# design.net
KiCad netlist of a schematic drawn in Altium Designer
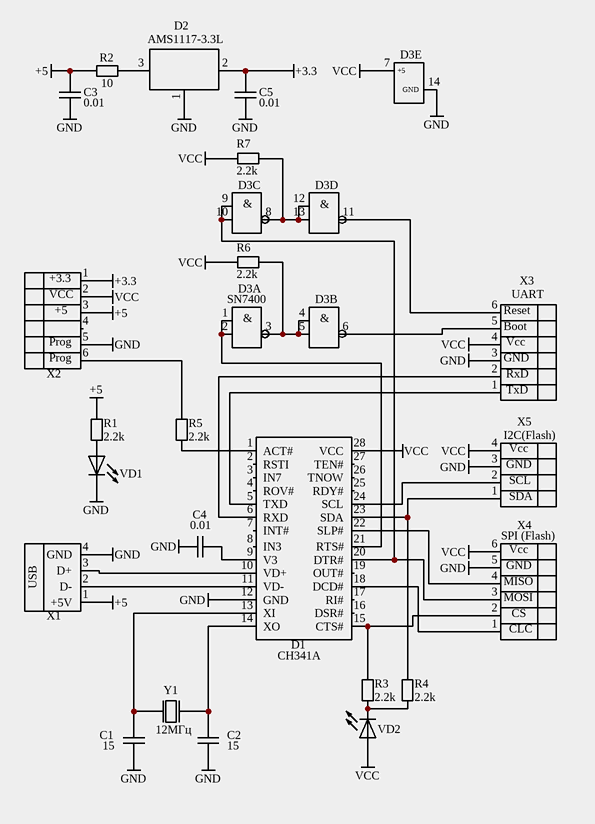
[diagram p0: схема.SchDoc]

(export (version "E")
  (design (tool "Eeschema 10.0.6"))
  (components
    (comp (ref "C1") (value "15") (footprint "0603") (libsource (lib "MainLib") (part "C")))
    (comp (ref "C2") (value "15") (footprint "0603") (libsource (lib "MainLib") (part "C")))
    (comp (ref "C3") (value "0.01") (footprint "0603") (libsource (lib "MainLib") (part "C")))
    (comp (ref "C4") (value "0.01") (footprint "0603") (libsource (lib "MainLib") (part "C")))
    (comp (ref "C5") (value "0.01") (footprint "0603") (libsource (lib "MainLib") (part "C")))
    (comp (ref "D1") (value "CH341A") (footprint "SOP127-28N") (libsource (lib "MainLib") (part "CH341A")))
    (comp (ref "D2")
      (value "AMS1117-3.3L")
      (footprint "SOT223-4N")
      (libsource (lib "MainLib") (part "AMS1117-3.3L"))
    )
    (comp (ref "D3") (value "SN7400") (footprint "SOP127-14N") (libsource (lib "MainLib") (part "SN7400")))
    (comp (ref "R1") (value "2.2k") (footprint "0603") (libsource (lib "MainLib") (part "R")))
    (comp (ref "R2") (value "10") (footprint "0603") (libsource (lib "MainLib") (part "R")))
    (comp (ref "R3") (value "2.2k") (footprint "0603") (libsource (lib "MainLib") (part "R")))
    (comp (ref "R4") (value "2.2k") (footprint "0603") (libsource (lib "MainLib") (part "R")))
    (comp (ref "R5") (value "2.2k") (footprint "0603") (libsource (lib "MainLib") (part "R")))
    (comp (ref "R6") (value "2.2k") (footprint "0603") (libsource (lib "MainLib") (part "R")))
    (comp (ref "R7") (value "2.2k") (footprint "0603") (libsource (lib "MainLib") (part "R")))
    (comp (ref "VD1")
      (value "LED SMD 0805")
      (footprint "Led Diode 0805")
      (libsource (lib "MainLib") (part "LED SMD 0805"))
    )
    (comp (ref "VD2")
      (value "LED SMD 0805")
      (footprint "Led Diode 0805")
      (libsource (lib "MainLib") (part "LED SMD 0805"))
    )
    (comp (ref "X1") (value "USB") (footprint "USB-ASM (DS1098-B)") (libsource (lib "MainLib") (part "USB")))
    (comp (ref "X2") (value "PLC-6") (footprint "PLC-6") (libsource (lib "MainLib") (part "PLC-6")))
    (comp (ref "X3") (value "UART") (footprint "PLC-6") (libsource (lib "") (part "PLC-6_1")))
    (comp (ref "X4") (value "SPI (Flash)") (footprint "PLC-6") (libsource (lib "") (part "PLC-6_1")))
    (comp (ref "X5") (value "I2C(Flash)") (footprint "PLC-4") (libsource (lib "MainLib") (part "PLC-4")))
    (comp (ref "Y1") (value "12МГц") (footprint "HC-49SM") (libsource (lib "MainLib") (part "BQ")))
  )
  (nets
    (net (code "1") (name "+3.3") (class "Default")
      (node (ref "C5") (pin "2") (pinfunction "2_2") (pintype "passive"))
      (node (ref "D2") (pin "2") (pinfunction "2_2") (pintype "passive"))
      (node (ref "X2") (pin "1") (pinfunction "1_1") (pintype "passive"))
    )
    (net (code "2") (name "+5") (class "Default")
      (node (ref "C3") (pin "2") (pinfunction "2_2") (pintype "passive"))
      (node (ref "R1") (pin "2") (pinfunction "2_2") (pintype "passive"))
      (node (ref "R2") (pin "1") (pinfunction "1_1") (pintype "passive"))
      (node (ref "X1") (pin "1") (pinfunction "+5V_1") (pintype "passive"))
      (node (ref "X2") (pin "3") (pinfunction "3_3") (pintype "passive"))
    )
    (net (code "3") (name "GND") (class "Default")
      (node (ref "C1") (pin "1") (pinfunction "1_1") (pintype "passive"))
      (node (ref "C2") (pin "1") (pinfunction "1_1") (pintype "passive"))
      (node (ref "C3") (pin "1") (pinfunction "1_1") (pintype "passive"))
      (node (ref "C4") (pin "2") (pinfunction "2_2") (pintype "passive"))
      (node (ref "C5") (pin "1") (pinfunction "1_1") (pintype "passive"))
      (node (ref "D1") (pin "12") (pinfunction "GND_12") (pintype "passive"))
      (node (ref "D2") (pin "1") (pinfunction "1_1") (pintype "passive"))
      (node (ref "D3") (pin "14") (pinfunction "GND_14") (pintype "passive"))
      (node (ref "VD1") (pin "K") (pinfunction "K_K") (pintype "passive"))
      (node (ref "X1") (pin "4") (pinfunction "GND_4") (pintype "passive"))
      (node (ref "X2") (pin "5") (pinfunction "5_5") (pintype "passive"))
      (node (ref "X3") (pin "3") (pinfunction "3_3") (pintype "passive"))
      (node (ref "X4") (pin "5") (pinfunction "5_5") (pintype "passive"))
      (node (ref "X5") (pin "3") (pinfunction "3_3") (pintype "passive"))
    )
    (net (code "4") (name "Net-(D1-ACT#)") (class "Default")
      (node (ref "D1") (pin "1") (pinfunction "ACT#_1") (pintype "passive"))
      (node (ref "R5") (pin "1") (pinfunction "1_1") (pintype "passive"))
    )
    (net (code "5") (name "Net-(D1-CTS#)") (class "Default")
      (node (ref "D1") (pin "15") (pinfunction "CTS#_15") (pintype "passive"))
      (node (ref "R3") (pin "2") (pinfunction "2_2") (pintype "passive"))
      (node (ref "X4") (pin "2") (pinfunction "2_2") (pintype "passive"))
    )
    (net (code "6") (name "Net-(D1-DCD#)") (class "Default")
      (node (ref "D1") (pin "18") (pinfunction "DCD#_18") (pintype "passive"))
      (node (ref "X4") (pin "1") (pinfunction "1_1") (pintype "passive"))
    )
    (net (code "7") (name "Net-(D1-DTR#)") (class "Default")
      (node (ref "D1") (pin "20") (pinfunction "DTR#_20") (pintype "passive"))
      (node (ref "D3") (pin "10") (pinfunction "10_10") (pintype "passive"))
      (node (ref "D3") (pin "9") (pinfunction "9_9") (pintype "passive"))
      (node (ref "X4") (pin "3") (pinfunction "3_3") (pintype "passive"))
    )
    (net (code "8") (name "Net-(D1-RTS#)") (class "Default")
      (node (ref "D1") (pin "21") (pinfunction "RTS#_21") (pintype "passive"))
      (node (ref "D3") (pin "1") (pinfunction "1_1") (pintype "passive"))
      (node (ref "D3") (pin "2") (pinfunction "2_2") (pintype "passive"))
    )
    (net (code "9") (name "Net-(D1-RXD)") (class "Default")
      (node (ref "D1") (pin "6") (pinfunction "RXD_6") (pintype "passive"))
      (node (ref "X3") (pin "2") (pinfunction "2_2") (pintype "passive"))
    )
    (net (code "10") (name "Net-(D1-SCL)") (class "Default")
      (node (ref "D1") (pin "24") (pinfunction "SCL_24") (pintype "passive"))
      (node (ref "X5") (pin "2") (pinfunction "2_2") (pintype "passive"))
    )
    (net (code "11") (name "Net-(D1-SDA)") (class "Default")
      (node (ref "D1") (pin "23") (pinfunction "SDA_23") (pintype "passive"))
      (node (ref "R4") (pin "2") (pinfunction "2_2") (pintype "passive"))
      (node (ref "X5") (pin "1") (pinfunction "1_1") (pintype "passive"))
    )
    (net (code "12") (name "Net-(D1-SLP#)") (class "Default")
      (node (ref "D1") (pin "22") (pinfunction "SLP#_22") (pintype "passive"))
      (node (ref "X4") (pin "4") (pinfunction "4_4") (pintype "passive"))
    )
    (net (code "13") (name "Net-(D1-TXD)") (class "Default")
      (node (ref "D1") (pin "5") (pinfunction "TXD_5") (pintype "passive"))
      (node (ref "X3") (pin "1") (pinfunction "1_1") (pintype "passive"))
    )
    (net (code "14") (name "Net-(D1-V3)") (class "Default")
      (node (ref "C4") (pin "1") (pinfunction "1_1") (pintype "passive"))
      (node (ref "D1") (pin "9") (pinfunction "V3_9") (pintype "passive"))
    )
    (net (code "15") (name "Net-(D1-VD+)") (class "Default")
      (node (ref "D1") (pin "10") (pinfunction "VD+_10") (pintype "passive"))
      (node (ref "X1") (pin "3") (pinfunction "D+_3") (pintype "passive"))
    )
    (net (code "16") (name "Net-(D1-VD-)") (class "Default")
      (node (ref "D1") (pin "11") (pinfunction "VD-_11") (pintype "passive"))
      (node (ref "X1") (pin "2") (pinfunction "D-_2") (pintype "passive"))
    )
    (net (code "17") (name "Net-(D1-XI)") (class "Default")
      (node (ref "C1") (pin "2") (pinfunction "2_2") (pintype "passive"))
      (node (ref "D1") (pin "13") (pinfunction "XI_13") (pintype "passive"))
      (node (ref "Y1") (pin "1") (pinfunction "1_1") (pintype "passive"))
    )
    (net (code "18") (name "Net-(D1-XO)") (class "Default")
      (node (ref "C2") (pin "2") (pinfunction "2_2") (pintype "passive"))
      (node (ref "D1") (pin "14") (pinfunction "XO_14") (pintype "passive"))
      (node (ref "Y1") (pin "2") (pinfunction "2_2") (pintype "passive"))
    )
    (net (code "19") (name "Net-(D2-Pad3)") (class "Default")
      (node (ref "D2") (pin "3") (pinfunction "3_3") (pintype "passive"))
      (node (ref "R2") (pin "2") (pinfunction "2_2") (pintype "passive"))
    )
    (net (code "20") (name "Net-(D3-Pad3)") (class "Default")
      (node (ref "D3") (pin "3") (pinfunction "3_3") (pintype "passive"))
      (node (ref "D3") (pin "4") (pinfunction "4_4") (pintype "passive"))
      (node (ref "D3") (pin "5") (pinfunction "5_5") (pintype "passive"))
      (node (ref "R6") (pin "1") (pinfunction "1_1") (pintype "passive"))
    )
    (net (code "21") (name "Net-(D3-Pad6)") (class "Default")
      (node (ref "D3") (pin "6") (pinfunction "6_6") (pintype "passive"))
      (node (ref "X3") (pin "5") (pinfunction "5_5") (pintype "passive"))
    )
    (net (code "22") (name "Net-(D3-Pad11)") (class "Default")
      (node (ref "D3") (pin "11") (pinfunction "11_11") (pintype "passive"))
      (node (ref "X3") (pin "6") (pinfunction "6_6") (pintype "passive"))
    )
    (net (code "23") (name "Net-(D3-Pad12)") (class "Default")
      (node (ref "D3") (pin "12") (pinfunction "12_12") (pintype "passive"))
      (node (ref "D3") (pin "13") (pinfunction "13_13") (pintype "passive"))
      (node (ref "D3") (pin "8") (pinfunction "8_8") (pintype "passive"))
      (node (ref "R7") (pin "1") (pinfunction "1_1") (pintype "passive"))
    )
    (net (code "24") (name "Net-(R1-Pad1)") (class "Default")
      (node (ref "R1") (pin "1") (pinfunction "1_1") (pintype "passive"))
      (node (ref "VD1") (pin "A") (pinfunction "A_A") (pintype "passive"))
    )
    (net (code "25") (name "Net-(R3-Pad1)") (class "Default")
      (node (ref "R3") (pin "1") (pinfunction "1_1") (pintype "passive"))
      (node (ref "R4") (pin "1") (pinfunction "1_1") (pintype "passive"))
      (node (ref "VD2") (pin "K") (pinfunction "K_K") (pintype "passive"))
    )
    (net (code "26") (name "Net-(R5-Pad2)") (class "Default")
      (node (ref "R5") (pin "2") (pinfunction "2_2") (pintype "passive"))
      (node (ref "X2") (pin "6") (pinfunction "6_6") (pintype "passive"))
    )
    (net (code "27") (name "VCC") (class "Default")
      (node (ref "D1") (pin "28") (pinfunction "VCC_28") (pintype "passive"))
      (node (ref "D3") (pin "7") (pinfunction "+5_7") (pintype "passive"))
      (node (ref "R6") (pin "2") (pinfunction "2_2") (pintype "passive"))
      (node (ref "R7") (pin "2") (pinfunction "2_2") (pintype "passive"))
      (node (ref "VD2") (pin "A") (pinfunction "A_A") (pintype "passive"))
      (node (ref "X2") (pin "2") (pinfunction "2_2") (pintype "passive"))
      (node (ref "X3") (pin "4") (pinfunction "4_4") (pintype "passive"))
      (node (ref "X4") (pin "6") (pinfunction "6_6") (pintype "passive"))
      (node (ref "X5") (pin "4") (pinfunction "4_4") (pintype "passive"))
    )
    (net (code "28") (name "unconnected-(D1-DSR#-Pad16)") (class "Default")
      (node (ref "D1") (pin "16") (pinfunction "DSR#_16") (pintype "passive"))
    )
    (net (code "29") (name "unconnected-(D1-IN3-Pad8)") (class "Default")
      (node (ref "D1") (pin "8") (pinfunction "IN3_8") (pintype "passive"))
    )
    (net (code "30") (name "unconnected-(D1-IN7-Pad3)") (class "Default")
      (node (ref "D1") (pin "3") (pinfunction "IN7_3") (pintype "passive"))
    )
    (net (code "31") (name "unconnected-(D1-INT#-Pad7)") (class "Default")
      (node (ref "D1") (pin "7") (pinfunction "INT#_7") (pintype "passive"))
    )
    (net (code "32") (name "unconnected-(D1-OUT#-Pad19)") (class "Default")
      (node (ref "D1") (pin "19") (pinfunction "OUT#_19") (pintype "passive"))
    )
    (net (code "33") (name "unconnected-(D1-RDY#-Pad25)") (class "Default")
      (node (ref "D1") (pin "25") (pinfunction "RDY#_25") (pintype "passive"))
    )
    (net (code "34") (name "unconnected-(D1-RI#-Pad17)") (class "Default")
      (node (ref "D1") (pin "17") (pinfunction "RI#_17") (pintype "passive"))
    )
    (net (code "35") (name "unconnected-(D1-ROV#-Pad4)") (class "Default")
      (node (ref "D1") (pin "4") (pinfunction "ROV#_4") (pintype "passive"))
    )
    (net (code "36") (name "unconnected-(D1-RSTI-Pad2)") (class "Default")
      (node (ref "D1") (pin "2") (pinfunction "RSTI_2") (pintype "passive"))
    )
    (net (code "37") (name "unconnected-(D1-TEN#-Pad27)") (class "Default")
      (node (ref "D1") (pin "27") (pinfunction "TEN#_27") (pintype "passive"))
    )
    (net (code "38") (name "unconnected-(D1-TNOW-Pad26)") (class "Default")
      (node (ref "D1") (pin "26") (pinfunction "TNOW_26") (pintype "passive"))
    )
    (net (code "39") (name "unconnected-(X2-Pad4)") (class "Default")
      (node (ref "X2") (pin "4") (pinfunction "4_4") (pintype "passive"))
    )
  )
)
